# Top.net
KiCad netlist of a schematic drawn in Altium Designer
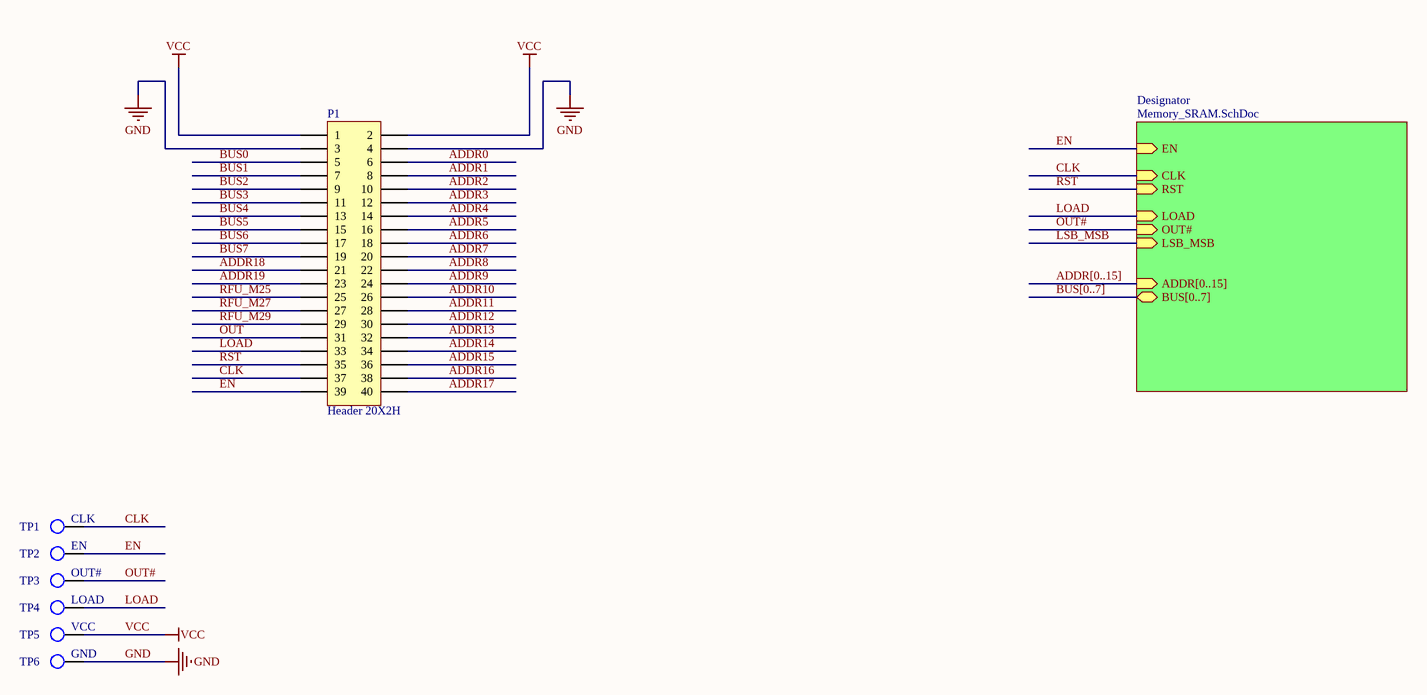
[diagram p0: Top.SchDoc]

(export (version "E")
  (design (tool "Eeschema 10.0.6"))
  (components
    (comp (ref "P1")
      (value "Header 20X2H")
      (footprint "HDR2X20H")
      (description "Header, 20-Pin, Dual row, Right Angle")
      (fields (field (name "PUBLISHER") "Altium Limited"))
      (libsource (lib "Miscellaneous Connectors") (part "Header 20X2H"))
    )
    (comp (ref "TP1") (value "CLK") (footprint "KSTN-5011_V") (libsource (lib "TP") (part "TP")))
    (comp (ref "TP2") (value "EN") (footprint "KSTN-5011_V") (libsource (lib "TP") (part "TP")))
    (comp (ref "TP3") (value "OUT#") (footprint "KSTN-5011_V") (libsource (lib "TP") (part "TP")))
    (comp (ref "TP4") (value "LOAD") (footprint "KSTN-5011_V") (libsource (lib "TP") (part "TP")))
    (comp (ref "TP5") (value "VCC") (footprint "KSTN-5011_V") (libsource (lib "TP") (part "TP")))
    (comp (ref "TP6") (value "GND") (footprint "KSTN-5011_V") (libsource (lib "TP") (part "TP")))
  )
  (nets
    (net (code "1") (name "/ADDR0") (class "Default")
      (node (ref "P1") (pin "6") (pinfunction "6_6") (pintype "passive"))
    )
    (net (code "2") (name "/ADDR1") (class "Default")
      (node (ref "P1") (pin "8") (pinfunction "8_8") (pintype "passive"))
    )
    (net (code "3") (name "/ADDR2") (class "Default")
      (node (ref "P1") (pin "10") (pinfunction "10_10") (pintype "passive"))
    )
    (net (code "4") (name "/ADDR3") (class "Default")
      (node (ref "P1") (pin "12") (pinfunction "12_12") (pintype "passive"))
    )
    (net (code "5") (name "/ADDR4") (class "Default")
      (node (ref "P1") (pin "14") (pinfunction "14_14") (pintype "passive"))
    )
    (net (code "6") (name "/ADDR5") (class "Default")
      (node (ref "P1") (pin "16") (pinfunction "16_16") (pintype "passive"))
    )
    (net (code "7") (name "/ADDR6") (class "Default")
      (node (ref "P1") (pin "18") (pinfunction "18_18") (pintype "passive"))
    )
    (net (code "8") (name "/ADDR7") (class "Default")
      (node (ref "P1") (pin "20") (pinfunction "20_20") (pintype "passive"))
    )
    (net (code "9") (name "/ADDR8") (class "Default")
      (node (ref "P1") (pin "22") (pinfunction "22_22") (pintype "passive"))
    )
    (net (code "10") (name "/ADDR9") (class "Default")
      (node (ref "P1") (pin "24") (pinfunction "24_24") (pintype "passive"))
    )
    (net (code "11") (name "/ADDR10") (class "Default")
      (node (ref "P1") (pin "26") (pinfunction "26_26") (pintype "passive"))
    )
    (net (code "12") (name "/ADDR11") (class "Default")
      (node (ref "P1") (pin "28") (pinfunction "28_28") (pintype "passive"))
    )
    (net (code "13") (name "/ADDR12") (class "Default")
      (node (ref "P1") (pin "30") (pinfunction "30_30") (pintype "passive"))
    )
    (net (code "14") (name "/ADDR13") (class "Default")
      (node (ref "P1") (pin "32") (pinfunction "32_32") (pintype "passive"))
    )
    (net (code "15") (name "/ADDR14") (class "Default")
      (node (ref "P1") (pin "34") (pinfunction "34_34") (pintype "passive"))
    )
    (net (code "16") (name "/ADDR15") (class "Default")
      (node (ref "P1") (pin "36") (pinfunction "36_36") (pintype "passive"))
    )
    (net (code "17") (name "/ADDR16") (class "Default")
      (node (ref "P1") (pin "38") (pinfunction "38_38") (pintype "passive"))
    )
    (net (code "18") (name "/ADDR17") (class "Default")
      (node (ref "P1") (pin "40") (pinfunction "40_40") (pintype "passive"))
    )
    (net (code "19") (name "/ADDR18") (class "Default")
      (node (ref "P1") (pin "21") (pinfunction "21_21") (pintype "passive"))
    )
    (net (code "20") (name "/ADDR19") (class "Default")
      (node (ref "P1") (pin "23") (pinfunction "23_23") (pintype "passive"))
    )
    (net (code "22") (name "/BUS0") (class "Default")
      (node (ref "P1") (pin "5") (pinfunction "5_5") (pintype "passive"))
    )
    (net (code "23") (name "/BUS1") (class "Default")
      (node (ref "P1") (pin "7") (pinfunction "7_7") (pintype "passive"))
    )
    (net (code "24") (name "/BUS2") (class "Default")
      (node (ref "P1") (pin "9") (pinfunction "9_9") (pintype "passive"))
    )
    (net (code "25") (name "/BUS3") (class "Default")
      (node (ref "P1") (pin "11") (pinfunction "11_11") (pintype "passive"))
    )
    (net (code "26") (name "/BUS4") (class "Default")
      (node (ref "P1") (pin "13") (pinfunction "13_13") (pintype "passive"))
    )
    (net (code "27") (name "/BUS5") (class "Default")
      (node (ref "P1") (pin "15") (pinfunction "15_15") (pintype "passive"))
    )
    (net (code "28") (name "/BUS6") (class "Default")
      (node (ref "P1") (pin "17") (pinfunction "17_17") (pintype "passive"))
    )
    (net (code "29") (name "/BUS7") (class "Default")
      (node (ref "P1") (pin "19") (pinfunction "19_19") (pintype "passive"))
    )
    (net (code "31") (name "/CLK") (class "Default")
      (node (ref "P1") (pin "37") (pinfunction "37_37") (pintype "passive"))
      (node (ref "TP1") (pin "1") (pintype "passive"))
    )
    (net (code "32") (name "/EN") (class "Default")
      (node (ref "P1") (pin "39") (pinfunction "39_39") (pintype "passive"))
      (node (ref "TP2") (pin "1") (pintype "passive"))
    )
    (net (code "33") (name "/LOAD") (class "Default")
      (node (ref "P1") (pin "33") (pinfunction "33_33") (pintype "passive"))
      (node (ref "TP4") (pin "1") (pintype "passive"))
    )
    (net (code "35") (name "/OUT#") (class "Default") (node (ref "TP3") (pin "1") (pintype "passive")))
    (net (code "36") (name "/RFU_M25") (class "Default")
      (node (ref "P1") (pin "25") (pinfunction "25_25") (pintype "passive"))
    )
    (net (code "37") (name "/RFU_M27") (class "Default")
      (node (ref "P1") (pin "27") (pinfunction "27_27") (pintype "passive"))
    )
    (net (code "38") (name "/RFU_M29") (class "Default")
      (node (ref "P1") (pin "29") (pinfunction "29_29") (pintype "passive"))
    )
    (net (code "39") (name "/RST") (class "Default")
      (node (ref "P1") (pin "35") (pinfunction "35_35") (pintype "passive"))
    )
    (net (code "40") (name "/~{OUT}") (class "Default")
      (node (ref "P1") (pin "31") (pinfunction "31_31") (pintype "passive"))
    )
    (net (code "41") (name "GND") (class "Default")
      (node (ref "P1") (pin "3") (pinfunction "3_3") (pintype "passive"))
      (node (ref "P1") (pin "4") (pinfunction "4_4") (pintype "passive"))
      (node (ref "TP6") (pin "1") (pintype "passive"))
    )
    (net (code "42") (name "VCC") (class "Default")
      (node (ref "P1") (pin "1") (pinfunction "1_1") (pintype "passive"))
      (node (ref "P1") (pin "2") (pinfunction "2_2") (pintype "passive"))
      (node (ref "TP5") (pin "1") (pintype "passive"))
    )
  )
)
